# Microcontroller_Schematic.net
KiCad netlist of a schematic drawn in Altium Designer
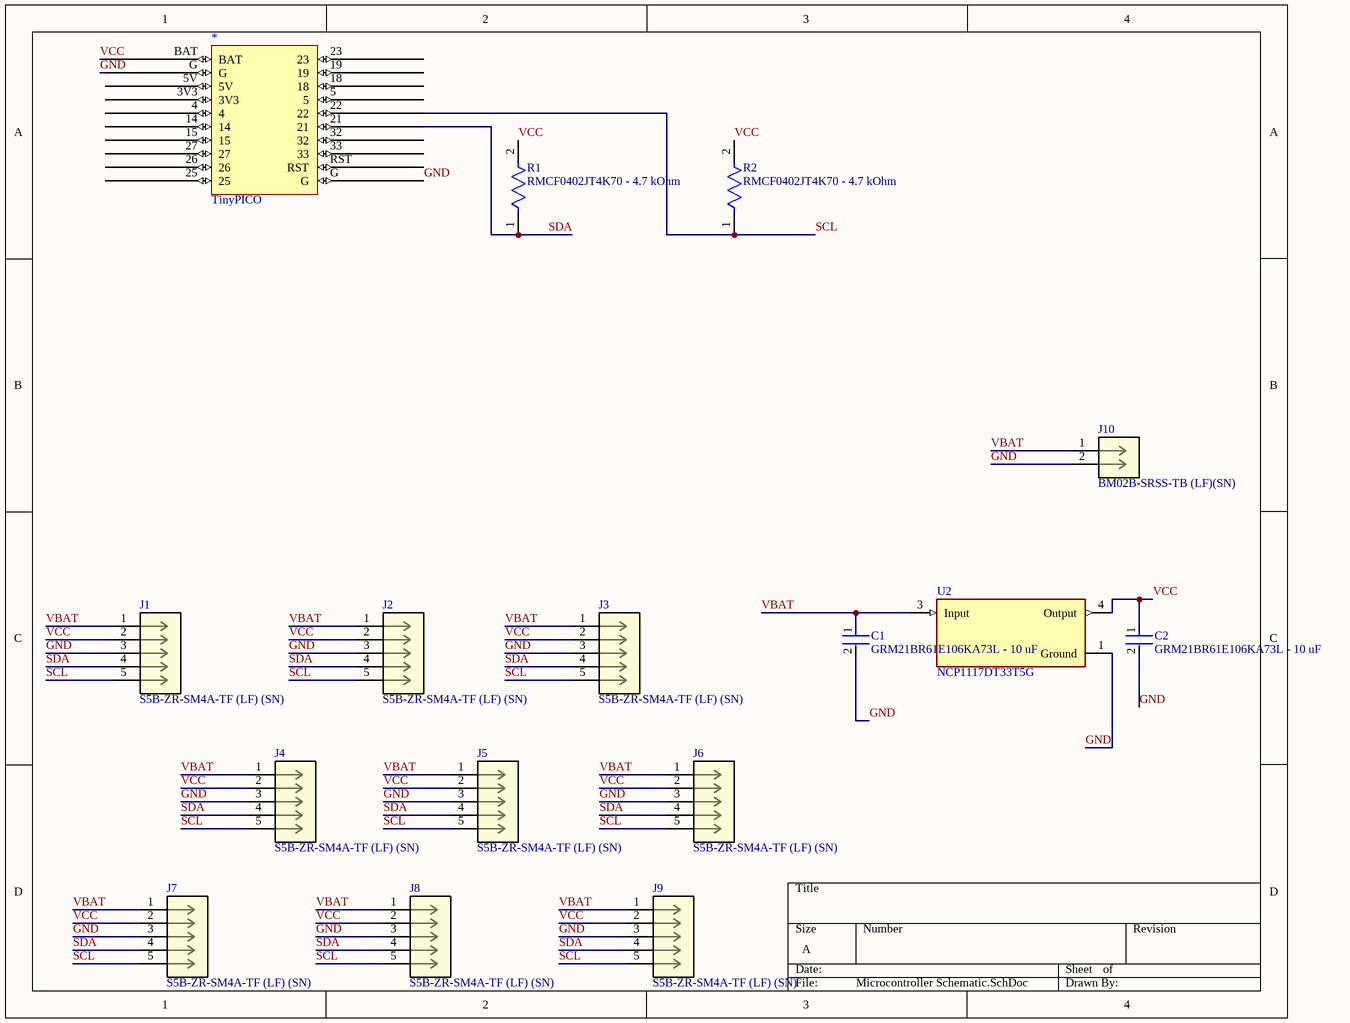
[diagram p0: Microcontroller Schematic.SchDoc]

(export (version "E")
  (design (tool "Eeschema 10.0.6"))
  (components
    (comp (ref "*")
      (value "TinyPICO")
      (footprint "TinyPICO Board")
      (libsource (lib "TinyPICO") (part "TinyPICO"))
    )
    (comp (ref "C1")
      (value "GRM21BR61E106KA73L - 10 uF")
      (footprint "FP-GRM21B-0_15-IPC_C")
      (description "Chip Multilayer Ceramic Capacitors for General Purpose, 0805, 10uF, X5R, 15%, 10%, 25V")
      (fields (field (name "VOLTAGE") "25V") (field (name "TOLERANCE") "10%"))
      (libsource (lib "Altium Content Vault") (part "b4654b650e69147ec39a6b967a45e02"))
    )
    (comp (ref "C2")
      (value "GRM21BR61E106KA73L - 10 uF")
      (footprint "FP-GRM21B-0_15-IPC_C")
      (description "Chip Multilayer Ceramic Capacitors for General Purpose, 0805, 10uF, X5R, 15%, 10%, 25V")
      (fields (field (name "VOLTAGE") "25V") (field (name "TOLERANCE") "10%"))
      (libsource (lib "Altium Content Vault") (part "b4654b650e69147ec39a6b967a45e02"))
    )
    (comp (ref "J1")
      (value "S5B-ZR-SM4A-TF (LF) (SN)")
      (footprint "CONN_S5B-ZR-SM4A-TF_JST")
      (description "No Description Available")
      (fields (field (name "COPYRIGHT") "Copyright (C) 2021 Ultra Librarian. All rights reserved."))
      (libsource (lib "S5B-ZR-SM4A-TF_LF__SN_") (part "S5B-ZR-SM4A-TF (LF) (SN)"))
    )
    (comp (ref "J2")
      (value "S5B-ZR-SM4A-TF (LF) (SN)")
      (footprint "CONN_S5B-ZR-SM4A-TF_JST")
      (description "No Description Available")
      (fields (field (name "COPYRIGHT") "Copyright (C) 2021 Ultra Librarian. All rights reserved."))
      (libsource (lib "S5B-ZR-SM4A-TF_LF__SN_") (part "S5B-ZR-SM4A-TF (LF) (SN)"))
    )
    (comp (ref "J3")
      (value "S5B-ZR-SM4A-TF (LF) (SN)")
      (footprint "CONN_S5B-ZR-SM4A-TF_JST")
      (description "No Description Available")
      (fields (field (name "COPYRIGHT") "Copyright (C) 2021 Ultra Librarian. All rights reserved."))
      (libsource (lib "S5B-ZR-SM4A-TF_LF__SN_") (part "S5B-ZR-SM4A-TF (LF) (SN)"))
    )
    (comp (ref "J4")
      (value "S5B-ZR-SM4A-TF (LF) (SN)")
      (footprint "CONN_S5B-ZR-SM4A-TF_JST")
      (description "No Description Available")
      (fields (field (name "COPYRIGHT") "Copyright (C) 2021 Ultra Librarian. All rights reserved."))
      (libsource (lib "S5B-ZR-SM4A-TF_LF__SN_") (part "S5B-ZR-SM4A-TF (LF) (SN)"))
    )
    (comp (ref "J5")
      (value "S5B-ZR-SM4A-TF (LF) (SN)")
      (footprint "CONN_S5B-ZR-SM4A-TF_JST")
      (description "No Description Available")
      (fields (field (name "COPYRIGHT") "Copyright (C) 2021 Ultra Librarian. All rights reserved."))
      (libsource (lib "S5B-ZR-SM4A-TF_LF__SN_") (part "S5B-ZR-SM4A-TF (LF) (SN)"))
    )
    (comp (ref "J6")
      (value "S5B-ZR-SM4A-TF (LF) (SN)")
      (footprint "CONN_S5B-ZR-SM4A-TF_JST")
      (description "No Description Available")
      (fields (field (name "COPYRIGHT") "Copyright (C) 2021 Ultra Librarian. All rights reserved."))
      (libsource (lib "S5B-ZR-SM4A-TF_LF__SN_") (part "S5B-ZR-SM4A-TF (LF) (SN)"))
    )
    (comp (ref "J7")
      (value "S5B-ZR-SM4A-TF (LF) (SN)")
      (footprint "CONN_S5B-ZR-SM4A-TF_JST")
      (description "No Description Available")
      (fields (field (name "COPYRIGHT") "Copyright (C) 2021 Ultra Librarian. All rights reserved."))
      (libsource (lib "S5B-ZR-SM4A-TF_LF__SN_") (part "S5B-ZR-SM4A-TF (LF) (SN)"))
    )
    (comp (ref "J8")
      (value "S5B-ZR-SM4A-TF (LF) (SN)")
      (footprint "CONN_S5B-ZR-SM4A-TF_JST")
      (description "No Description Available")
      (fields (field (name "COPYRIGHT") "Copyright (C) 2021 Ultra Librarian. All rights reserved."))
      (libsource (lib "S5B-ZR-SM4A-TF_LF__SN_") (part "S5B-ZR-SM4A-TF (LF) (SN)"))
    )
    (comp (ref "J9")
      (value "S5B-ZR-SM4A-TF (LF) (SN)")
      (footprint "CONN_S5B-ZR-SM4A-TF_JST")
      (description "No Description Available")
      (fields (field (name "COPYRIGHT") "Copyright (C) 2021 Ultra Librarian. All rights reserved."))
      (libsource (lib "S5B-ZR-SM4A-TF_LF__SN_") (part "S5B-ZR-SM4A-TF (LF) (SN)"))
    )
    (comp (ref "J10")
      (value "BM02B-SRSS-TB (LF)(SN)")
      (footprint "CONN_BM02B-SRSS-TB_JST")
      (description "No Description Available")
      (fields (field (name "COPYRIGHT") "Copyright (C) 2021 Ultra Librarian. All rights reserved."))
      (libsource (lib "BM02B-SRSS-TB_LF__SN_") (part "BM02B-SRSS-TB (LF)(SN)"))
    )
    (comp (ref "R1")
      (value "RMCF0402JT4K70 - 4.7 kOhm")
      (footprint "FP-RMCF0402-MFG")
      (description "4.7kΩ ±5% 0.063W 0402 Thick Film Chip Resistor AEC-Q200 compliant")
      (fields (field (name "TOLERANCE") "5%"))
      (libsource (lib "Altium Content Vault") (part "1029c3af85768c4190bb7ad29bc67b5"))
    )
    (comp (ref "R2")
      (value "RMCF0402JT4K70 - 4.7 kOhm")
      (footprint "FP-RMCF0402-MFG")
      (description "4.7kΩ ±5% 0.063W 0402 Thick Film Chip Resistor AEC-Q200 compliant")
      (fields (field (name "TOLERANCE") "5%"))
      (libsource (lib "Altium Content Vault") (part "1029c3af85768c4190bb7ad29bc67b5"))
    )
    (comp (ref "U2")
      (value "NCP1117DT33T5G")
      (footprint "FP-369C-MFG")
      (description "IC REG LINEAR 3.3V 1A DPAK")
      (libsource (lib "Altium Content Vault") (part "f1512ae604efdd4bd306cab1b45f420"))
    )
  )
  (nets
    (net (code "1") (name "/GND") (class "Default")
      (node (ref "*") (pin "G") (pinfunction "G_G") (pintype "bidirectional"))
      (node (ref "C1") (pin "2") (pinfunction "2_2") (pintype "passive"))
      (node (ref "C2") (pin "2") (pinfunction "2_2") (pintype "passive"))
      (node (ref "J1") (pin "3") (pinfunction "3_3") (pintype "passive"))
      (node (ref "J10") (pin "2") (pinfunction "2_2") (pintype "passive"))
      (node (ref "J2") (pin "3") (pinfunction "3_3") (pintype "passive"))
      (node (ref "J3") (pin "3") (pinfunction "3_3") (pintype "passive"))
      (node (ref "J4") (pin "3") (pinfunction "3_3") (pintype "passive"))
      (node (ref "J5") (pin "3") (pinfunction "3_3") (pintype "passive"))
      (node (ref "J6") (pin "3") (pinfunction "3_3") (pintype "passive"))
      (node (ref "J7") (pin "3") (pinfunction "3_3") (pintype "passive"))
      (node (ref "J8") (pin "3") (pinfunction "3_3") (pintype "passive"))
      (node (ref "J9") (pin "3") (pinfunction "3_3") (pintype "passive"))
      (node (ref "U2") (pin "1") (pinfunction "Ground_1") (pintype "power_in"))
    )
    (net (code "2") (name "/SCL") (class "Default")
      (node (ref "*") (pin "22") (pinfunction "22_22") (pintype "bidirectional"))
      (node (ref "J1") (pin "5") (pinfunction "5_5") (pintype "passive"))
      (node (ref "J2") (pin "5") (pinfunction "5_5") (pintype "passive"))
      (node (ref "J3") (pin "5") (pinfunction "5_5") (pintype "passive"))
      (node (ref "J4") (pin "5") (pinfunction "5_5") (pintype "passive"))
      (node (ref "J5") (pin "5") (pinfunction "5_5") (pintype "passive"))
      (node (ref "J6") (pin "5") (pinfunction "5_5") (pintype "passive"))
      (node (ref "J7") (pin "5") (pinfunction "5_5") (pintype "passive"))
      (node (ref "J8") (pin "5") (pinfunction "5_5") (pintype "passive"))
      (node (ref "J9") (pin "5") (pinfunction "5_5") (pintype "passive"))
      (node (ref "R2") (pin "1") (pinfunction "1_1") (pintype "passive"))
    )
    (net (code "3") (name "/SDA") (class "Default")
      (node (ref "*") (pin "21") (pinfunction "21_21") (pintype "bidirectional"))
      (node (ref "J1") (pin "4") (pinfunction "4_4") (pintype "passive"))
      (node (ref "J2") (pin "4") (pinfunction "4_4") (pintype "passive"))
      (node (ref "J3") (pin "4") (pinfunction "4_4") (pintype "passive"))
      (node (ref "J4") (pin "4") (pinfunction "4_4") (pintype "passive"))
      (node (ref "J5") (pin "4") (pinfunction "4_4") (pintype "passive"))
      (node (ref "J6") (pin "4") (pinfunction "4_4") (pintype "passive"))
      (node (ref "J7") (pin "4") (pinfunction "4_4") (pintype "passive"))
      (node (ref "J8") (pin "4") (pinfunction "4_4") (pintype "passive"))
      (node (ref "J9") (pin "4") (pinfunction "4_4") (pintype "passive"))
      (node (ref "R1") (pin "1") (pinfunction "1_1") (pintype "passive"))
    )
    (net (code "4") (name "/VBAT") (class "Default")
      (node (ref "C1") (pin "1") (pinfunction "1_1") (pintype "passive"))
      (node (ref "J1") (pin "1") (pinfunction "1_1") (pintype "passive"))
      (node (ref "J10") (pin "1") (pinfunction "1_1") (pintype "passive"))
      (node (ref "J2") (pin "1") (pinfunction "1_1") (pintype "passive"))
      (node (ref "J3") (pin "1") (pinfunction "1_1") (pintype "passive"))
      (node (ref "J4") (pin "1") (pinfunction "1_1") (pintype "passive"))
      (node (ref "J5") (pin "1") (pinfunction "1_1") (pintype "passive"))
      (node (ref "J6") (pin "1") (pinfunction "1_1") (pintype "passive"))
      (node (ref "J7") (pin "1") (pinfunction "1_1") (pintype "passive"))
      (node (ref "J8") (pin "1") (pinfunction "1_1") (pintype "passive"))
      (node (ref "J9") (pin "1") (pinfunction "1_1") (pintype "passive"))
      (node (ref "U2") (pin "3") (pinfunction "Input_3") (pintype "input"))
    )
    (net (code "5") (name "/VCC") (class "Default")
      (node (ref "*") (pin "BAT") (pinfunction "BAT_BAT") (pintype "bidirectional"))
      (node (ref "C2") (pin "1") (pinfunction "1_1") (pintype "passive"))
      (node (ref "J1") (pin "2") (pinfunction "2_2") (pintype "passive"))
      (node (ref "J2") (pin "2") (pinfunction "2_2") (pintype "passive"))
      (node (ref "J3") (pin "2") (pinfunction "2_2") (pintype "passive"))
      (node (ref "J4") (pin "2") (pinfunction "2_2") (pintype "passive"))
      (node (ref "J5") (pin "2") (pinfunction "2_2") (pintype "passive"))
      (node (ref "J6") (pin "2") (pinfunction "2_2") (pintype "passive"))
      (node (ref "J7") (pin "2") (pinfunction "2_2") (pintype "passive"))
      (node (ref "J8") (pin "2") (pinfunction "2_2") (pintype "passive"))
      (node (ref "J9") (pin "2") (pinfunction "2_2") (pintype "passive"))
      (node (ref "R1") (pin "2") (pinfunction "2_2") (pintype "passive"))
      (node (ref "R2") (pin "2") (pinfunction "2_2") (pintype "passive"))
      (node (ref "U2") (pin "4") (pinfunction "Output_4") (pintype "output"))
    )
    (net (code "6") (name "unconnected-(*-Pad3V3)") (class "Default")
      (node (ref "*") (pin "3V3") (pinfunction "3V3_3V3") (pintype "bidirectional"))
    )
    (net (code "7") (name "unconnected-(*-Pad4)") (class "Default")
      (node (ref "*") (pin "4") (pinfunction "4_4") (pintype "bidirectional"))
    )
    (net (code "8") (name "unconnected-(*-Pad5)") (class "Default")
      (node (ref "*") (pin "5") (pinfunction "5_5") (pintype "bidirectional"))
    )
    (net (code "9") (name "unconnected-(*-Pad5V)") (class "Default")
      (node (ref "*") (pin "5V") (pinfunction "5V_5V") (pintype "bidirectional"))
    )
    (net (code "10") (name "unconnected-(*-Pad14)") (class "Default")
      (node (ref "*") (pin "14") (pinfunction "14_14") (pintype "bidirectional"))
    )
    (net (code "11") (name "unconnected-(*-Pad15)") (class "Default")
      (node (ref "*") (pin "15") (pinfunction "15_15") (pintype "bidirectional"))
    )
    (net (code "12") (name "unconnected-(*-Pad18)") (class "Default")
      (node (ref "*") (pin "18") (pinfunction "18_18") (pintype "bidirectional"))
    )
    (net (code "13") (name "unconnected-(*-Pad19)") (class "Default")
      (node (ref "*") (pin "19") (pinfunction "19_19") (pintype "bidirectional"))
    )
    (net (code "14") (name "unconnected-(*-Pad23)") (class "Default")
      (node (ref "*") (pin "23") (pinfunction "23_23") (pintype "bidirectional"))
    )
    (net (code "15") (name "unconnected-(*-Pad25)") (class "Default")
      (node (ref "*") (pin "25") (pinfunction "25_25") (pintype "bidirectional"))
    )
    (net (code "16") (name "unconnected-(*-Pad26)") (class "Default")
      (node (ref "*") (pin "26") (pinfunction "26_26") (pintype "bidirectional"))
    )
    (net (code "17") (name "unconnected-(*-Pad27)") (class "Default")
      (node (ref "*") (pin "27") (pinfunction "27_27") (pintype "bidirectional"))
    )
    (net (code "18") (name "unconnected-(*-Pad32)") (class "Default")
      (node (ref "*") (pin "32") (pinfunction "32_32") (pintype "bidirectional"))
    )
    (net (code "19") (name "unconnected-(*-Pad33)") (class "Default")
      (node (ref "*") (pin "33") (pinfunction "33_33") (pintype "bidirectional"))
    )
    (net (code "20") (name "unconnected-(*-PadRST)") (class "Default")
      (node (ref "*") (pin "RST") (pinfunction "RST_RST") (pintype "bidirectional"))
    )
  )
)
